# robotModule.net
KiCad netlist of a schematic drawn in EAGLE
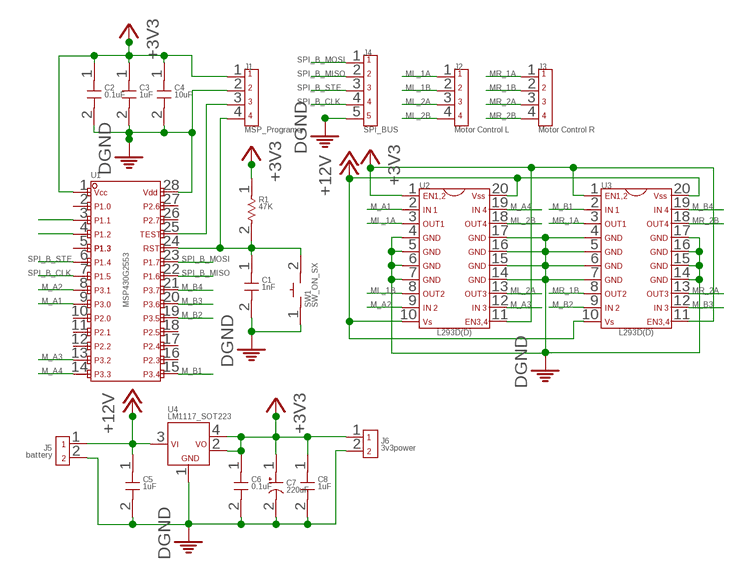
[diagram p0: schematic, sheet 1]

(export (version "E")
  (design (tool "Eeschema 10.0.6"))
  (components
    (comp (ref "C1")
      (value "1nF")
      (footprint "eagle-import:0805")
      (libsource (lib "eagle-import") (part "CAPACITOR_FIXED_0805"))
    )
    (comp (ref "C2")
      (value "0.1uF")
      (footprint "eagle-import:0805")
      (libsource (lib "eagle-import") (part "CAPACITOR_FIXED_0805"))
    )
    (comp (ref "C3")
      (value "1uF")
      (footprint "eagle-import:0805")
      (libsource (lib "eagle-import") (part "CAPACITOR_FIXED_0805"))
    )
    (comp (ref "C4")
      (value "10uF")
      (footprint "eagle-import:0805")
      (libsource (lib "eagle-import") (part "CAPACITOR_FIXED_0805"))
    )
    (comp (ref "C5")
      (value "1uF")
      (footprint "eagle-import:0805")
      (libsource (lib "eagle-import") (part "CAPACITOR_FIXED_0805"))
    )
    (comp (ref "C6")
      (value "0.1uF")
      (footprint "eagle-import:0805")
      (libsource (lib "eagle-import") (part "CAPACITOR_FIXED_0805"))
    )
    (comp (ref "C7")
      (value "220uF")
      (footprint "eagle-import:CAP_530_530")
      (libsource (lib "eagle-import") (part "CAPACITOR_POLARIZED_530_530"))
    )
    (comp (ref "C8")
      (value "1uF")
      (footprint "eagle-import:0805")
      (libsource (lib "eagle-import") (part "CAPACITOR_FIXED_0805"))
    )
    (comp (ref "J1")
      (value "MSP_Programer")
      (footprint "eagle-import:CON_HEADER_4_100")
      (libsource (lib "eagle-import") (part "CON_HEADER_4PIN_100"))
    )
    (comp (ref "J2")
      (value "Motor Control L")
      (footprint "eagle-import:CON_HEADER_4_100")
      (libsource (lib "eagle-import") (part "CON_HEADER_4PIN_100"))
    )
    (comp (ref "J3")
      (value "Motor Control R")
      (footprint "eagle-import:CON_HEADER_4_100")
      (libsource (lib "eagle-import") (part "CON_HEADER_4PIN_100"))
    )
    (comp (ref "J4")
      (value "SPI_BUS")
      (footprint "eagle-import:CON_HEADER_5_100")
      (libsource (lib "eagle-import") (part "CON_HEADER_5PIN_100"))
    )
    (comp (ref "J5")
      (value "battery")
      (footprint "eagle-import:CON_HEADER_2_200")
      (libsource (lib "eagle-import") (part "CON_HEADER_2PIN_200"))
    )
    (comp (ref "J6")
      (value "3v3power")
      (footprint "eagle-import:CON_HEADER_2_100")
      (libsource (lib "eagle-import") (part "CON_HEADER_2PIN_100"))
    )
    (comp (ref "R1")
      (value "47K")
      (footprint "eagle-import:0805")
      (libsource (lib "eagle-import") (part "RESISTOR_0805"))
    )
    (comp (ref "SW1")
      (value "SW_ON_SX")
      (footprint "eagle-import:SW_S")
      (libsource (lib "eagle-import") (part "SW_ON_SX"))
    )
    (comp (ref "U1")
      (value "MSP430G2553_24IO_28PIN_TSSOP")
      (footprint "eagle-import:TSSOP_28")
      (libsource (lib "eagle-import") (part "MSP430G2553_24IO_28PIN_TSSOP"))
    )
    (comp (ref "U2")
      (value "L293D(D)_ST_SMD")
      (footprint "eagle-import:SOIC_20")
      (libsource (lib "eagle-import") (part "L293D(D)_ST_SMD"))
    )
    (comp (ref "U3")
      (value "L293D(D)_ST_SMD")
      (footprint "eagle-import:SOIC_20")
      (libsource (lib "eagle-import") (part "L293D(D)_ST_SMD"))
    )
    (comp (ref "U4")
      (value "LM1117_SOT223")
      (footprint "eagle-import:SOT_233_4")
      (libsource (lib "eagle-import") (part "LM1117_SOT223"))
    )
  )
  (nets
    (net (code "1") (name "+3V3") (class "Default")
      (node (ref "C2") (pin "1") (pinfunction "1_1") (pintype "passive"))
      (node (ref "C3") (pin "1") (pinfunction "1_1") (pintype "passive"))
      (node (ref "C4") (pin "1") (pinfunction "1_1") (pintype "passive"))
      (node (ref "C6") (pin "1") (pinfunction "1_1") (pintype "passive"))
      (node (ref "C7") (pin "1") (pinfunction "1_1") (pintype "passive"))
      (node (ref "C8") (pin "1") (pinfunction "1_1") (pintype "passive"))
      (node (ref "J1") (pin "1") (pinfunction "1_1") (pintype "passive"))
      (node (ref "J6") (pin "1") (pinfunction "1_1") (pintype "passive"))
      (node (ref "R1") (pin "1") (pinfunction "1_1") (pintype "passive"))
      (node (ref "U1") (pin "1") (pinfunction "1_1") (pintype "passive"))
      (node (ref "U2") (pin "1") (pinfunction "1_1") (pintype "passive"))
      (node (ref "U2") (pin "11") (pinfunction "11_11") (pintype "passive"))
      (node (ref "U3") (pin "1") (pinfunction "1_1") (pintype "passive"))
      (node (ref "U3") (pin "11") (pinfunction "11_11") (pintype "passive"))
      (node (ref "U4") (pin "2") (pinfunction "2_2") (pintype "passive"))
      (node (ref "U4") (pin "4") (pinfunction "4_4") (pintype "passive"))
    )
    (net (code "2") (name "+12V") (class "Default")
      (node (ref "C5") (pin "1") (pinfunction "1_1") (pintype "passive"))
      (node (ref "J5") (pin "1") (pinfunction "1_1") (pintype "passive"))
      (node (ref "U2") (pin "10") (pinfunction "10_10") (pintype "passive"))
      (node (ref "U2") (pin "20") (pinfunction "20_20") (pintype "passive"))
      (node (ref "U3") (pin "10") (pinfunction "10_10") (pintype "passive"))
      (node (ref "U3") (pin "20") (pinfunction "20_20") (pintype "passive"))
      (node (ref "U4") (pin "3") (pinfunction "3_3") (pintype "input"))
    )
    (net (code "3") (name "/ML_1A") (class "Default")
      (node (ref "J2") (pin "1") (pinfunction "1_1") (pintype "passive"))
      (node (ref "U2") (pin "3") (pinfunction "3_3") (pintype "passive"))
    )
    (net (code "4") (name "/ML_1B") (class "Default")
      (node (ref "J2") (pin "2") (pinfunction "2_2") (pintype "passive"))
      (node (ref "U2") (pin "8") (pinfunction "8_8") (pintype "passive"))
    )
    (net (code "5") (name "/ML_2A") (class "Default")
      (node (ref "J2") (pin "3") (pinfunction "3_3") (pintype "passive"))
      (node (ref "U2") (pin "13") (pinfunction "13_13") (pintype "passive"))
    )
    (net (code "6") (name "/ML_2B") (class "Default")
      (node (ref "J2") (pin "4") (pinfunction "4_4") (pintype "passive"))
      (node (ref "U2") (pin "18") (pinfunction "18_18") (pintype "passive"))
    )
    (net (code "7") (name "/MR_1A") (class "Default")
      (node (ref "J3") (pin "1") (pinfunction "1_1") (pintype "passive"))
      (node (ref "U3") (pin "3") (pinfunction "3_3") (pintype "passive"))
    )
    (net (code "8") (name "/MR_1B") (class "Default")
      (node (ref "J3") (pin "2") (pinfunction "2_2") (pintype "passive"))
      (node (ref "U3") (pin "8") (pinfunction "8_8") (pintype "passive"))
    )
    (net (code "9") (name "/MR_2A") (class "Default")
      (node (ref "J3") (pin "3") (pinfunction "3_3") (pintype "passive"))
      (node (ref "U3") (pin "13") (pinfunction "13_13") (pintype "passive"))
    )
    (net (code "10") (name "/MR_2B") (class "Default")
      (node (ref "J3") (pin "4") (pinfunction "4_4") (pintype "passive"))
      (node (ref "U3") (pin "18") (pinfunction "18_18") (pintype "passive"))
    )
    (net (code "11") (name "/M_A1") (class "Default")
      (node (ref "U1") (pin "9") (pinfunction "9_9") (pintype "passive"))
      (node (ref "U2") (pin "2") (pinfunction "2_2") (pintype "passive"))
    )
    (net (code "12") (name "/M_A2") (class "Default")
      (node (ref "U1") (pin "8") (pinfunction "8_8") (pintype "passive"))
      (node (ref "U2") (pin "9") (pinfunction "9_9") (pintype "passive"))
    )
    (net (code "13") (name "/M_A3") (class "Default")
      (node (ref "U1") (pin "13") (pinfunction "13_13") (pintype "passive"))
      (node (ref "U2") (pin "12") (pinfunction "12_12") (pintype "passive"))
    )
    (net (code "14") (name "/M_A4") (class "Default")
      (node (ref "U1") (pin "14") (pinfunction "14_14") (pintype "passive"))
      (node (ref "U2") (pin "19") (pinfunction "19_19") (pintype "passive"))
    )
    (net (code "15") (name "/M_B1") (class "Default")
      (node (ref "U1") (pin "15") (pinfunction "15_15") (pintype "passive"))
      (node (ref "U3") (pin "2") (pinfunction "2_2") (pintype "passive"))
    )
    (net (code "16") (name "/M_B2") (class "Default")
      (node (ref "U1") (pin "19") (pinfunction "19_19") (pintype "passive"))
      (node (ref "U3") (pin "9") (pinfunction "9_9") (pintype "passive"))
    )
    (net (code "17") (name "/M_B3") (class "Default")
      (node (ref "U1") (pin "20") (pinfunction "20_20") (pintype "passive"))
      (node (ref "U3") (pin "12") (pinfunction "12_12") (pintype "passive"))
    )
    (net (code "18") (name "/M_B4") (class "Default")
      (node (ref "U1") (pin "21") (pinfunction "21_21") (pintype "passive"))
      (node (ref "U3") (pin "19") (pinfunction "19_19") (pintype "passive"))
    )
    (net (code "19") (name "/SPI_B_CLK") (class "Default")
      (node (ref "J4") (pin "4") (pinfunction "4_4") (pintype "passive"))
      (node (ref "U1") (pin "7") (pinfunction "7_7") (pintype "passive"))
    )
    (net (code "20") (name "/SPI_B_MISO") (class "Default")
      (node (ref "J4") (pin "2") (pinfunction "2_2") (pintype "passive"))
      (node (ref "U1") (pin "22") (pinfunction "22_22") (pintype "passive"))
    )
    (net (code "21") (name "/SPI_B_MOSI") (class "Default")
      (node (ref "J4") (pin "1") (pinfunction "1_1") (pintype "passive"))
      (node (ref "U1") (pin "23") (pinfunction "23_23") (pintype "passive"))
    )
    (net (code "22") (name "/SPI_B_STE") (class "Default")
      (node (ref "J4") (pin "3") (pinfunction "3_3") (pintype "passive"))
      (node (ref "U1") (pin "6") (pinfunction "6_6") (pintype "passive"))
    )
    (net (code "23") (name "DGND") (class "Default")
      (node (ref "C1") (pin "2") (pinfunction "2_2") (pintype "passive"))
      (node (ref "C2") (pin "2") (pinfunction "2_2") (pintype "passive"))
      (node (ref "C3") (pin "2") (pinfunction "2_2") (pintype "passive"))
      (node (ref "C4") (pin "2") (pinfunction "2_2") (pintype "passive"))
      (node (ref "C5") (pin "2") (pinfunction "2_2") (pintype "passive"))
      (node (ref "C6") (pin "2") (pinfunction "2_2") (pintype "passive"))
      (node (ref "C7") (pin "2") (pinfunction "2_2") (pintype "passive"))
      (node (ref "C8") (pin "2") (pinfunction "2_2") (pintype "passive"))
      (node (ref "J1") (pin "2") (pinfunction "2_2") (pintype "passive"))
      (node (ref "J4") (pin "5") (pinfunction "5_5") (pintype "passive"))
      (node (ref "J5") (pin "2") (pinfunction "2_2") (pintype "passive"))
      (node (ref "J6") (pin "2") (pinfunction "2_2") (pintype "passive"))
      (node (ref "SW1") (pin "1") (pinfunction "1_1") (pintype "passive"))
      (node (ref "U1") (pin "28") (pinfunction "P$7_28") (pintype "passive"))
      (node (ref "U2") (pin "14") (pinfunction "14_14") (pintype "passive"))
      (node (ref "U2") (pin "15") (pinfunction "15_15") (pintype "passive"))
      (node (ref "U2") (pin "16") (pinfunction "16_16") (pintype "passive"))
      (node (ref "U2") (pin "17") (pinfunction "17_17") (pintype "passive"))
      (node (ref "U2") (pin "4") (pinfunction "4_4") (pintype "passive"))
      (node (ref "U2") (pin "5") (pinfunction "5_5") (pintype "passive"))
      (node (ref "U2") (pin "6") (pinfunction "6_6") (pintype "passive"))
      (node (ref "U2") (pin "7") (pinfunction "7_7") (pintype "passive"))
      (node (ref "U3") (pin "14") (pinfunction "14_14") (pintype "passive"))
      (node (ref "U3") (pin "15") (pinfunction "15_15") (pintype "passive"))
      (node (ref "U3") (pin "16") (pinfunction "16_16") (pintype "passive"))
      (node (ref "U3") (pin "17") (pinfunction "17_17") (pintype "passive"))
      (node (ref "U3") (pin "4") (pinfunction "4_4") (pintype "passive"))
      (node (ref "U3") (pin "5") (pinfunction "5_5") (pintype "passive"))
      (node (ref "U3") (pin "6") (pinfunction "6_6") (pintype "passive"))
      (node (ref "U3") (pin "7") (pinfunction "7_7") (pintype "passive"))
      (node (ref "U4") (pin "1") (pinfunction "1_1") (pintype "passive"))
    )
    (net (code "24") (name "Net-(C1-Pad1)") (class "Default")
      (node (ref "C1") (pin "1") (pinfunction "1_1") (pintype "passive"))
      (node (ref "J1") (pin "4") (pinfunction "4_4") (pintype "passive"))
      (node (ref "R1") (pin "2") (pinfunction "2_2") (pintype "passive"))
      (node (ref "SW1") (pin "2") (pinfunction "2_2") (pintype "passive"))
      (node (ref "U1") (pin "24") (pinfunction "24_24") (pintype "passive"))
    )
    (net (code "25") (name "Net-(J1-Pad3)") (class "Default")
      (node (ref "J1") (pin "3") (pinfunction "3_3") (pintype "passive"))
      (node (ref "U1") (pin "25") (pinfunction "25_25") (pintype "passive"))
    )
    (net (code "26") (name "unconnected-(U1-Pad2)") (class "Default")
      (node (ref "U1") (pin "2") (pinfunction "2_2") (pintype "passive"))
    )
    (net (code "27") (name "unconnected-(U1-Pad3)") (class "Default")
      (node (ref "U1") (pin "3") (pinfunction "3_3") (pintype "passive"))
    )
    (net (code "28") (name "unconnected-(U1-Pad4)") (class "Default")
      (node (ref "U1") (pin "4") (pinfunction "4_4") (pintype "passive"))
    )
    (net (code "29") (name "unconnected-(U1-Pad5)") (class "Default")
      (node (ref "U1") (pin "5") (pinfunction "5_5") (pintype "passive"))
    )
    (net (code "30") (name "unconnected-(U1-Pad10)") (class "Default")
      (node (ref "U1") (pin "10") (pinfunction "10_10") (pintype "passive"))
    )
    (net (code "31") (name "unconnected-(U1-Pad11)") (class "Default")
      (node (ref "U1") (pin "11") (pinfunction "11_11") (pintype "passive"))
    )
    (net (code "32") (name "unconnected-(U1-Pad12)") (class "Default")
      (node (ref "U1") (pin "12") (pinfunction "12_12") (pintype "passive"))
    )
    (net (code "33") (name "unconnected-(U1-Pad16)") (class "Default")
      (node (ref "U1") (pin "16") (pinfunction "16_16") (pintype "passive"))
    )
    (net (code "34") (name "unconnected-(U1-Pad17)") (class "Default")
      (node (ref "U1") (pin "17") (pinfunction "17_17") (pintype "passive"))
    )
    (net (code "35") (name "unconnected-(U1-Pad18)") (class "Default")
      (node (ref "U1") (pin "18") (pinfunction "18_18") (pintype "passive"))
    )
    (net (code "36") (name "unconnected-(U1-Pad26)") (class "Default")
      (node (ref "U1") (pin "26") (pinfunction "26_26") (pintype "passive"))
    )
    (net (code "37") (name "unconnected-(U1-Pad27)") (class "Default")
      (node (ref "U1") (pin "27") (pinfunction "27_27") (pintype "passive"))
    )
  )
)
